# STM32F411CEU6.net
KiCad netlist of a schematic drawn in Altium Designer
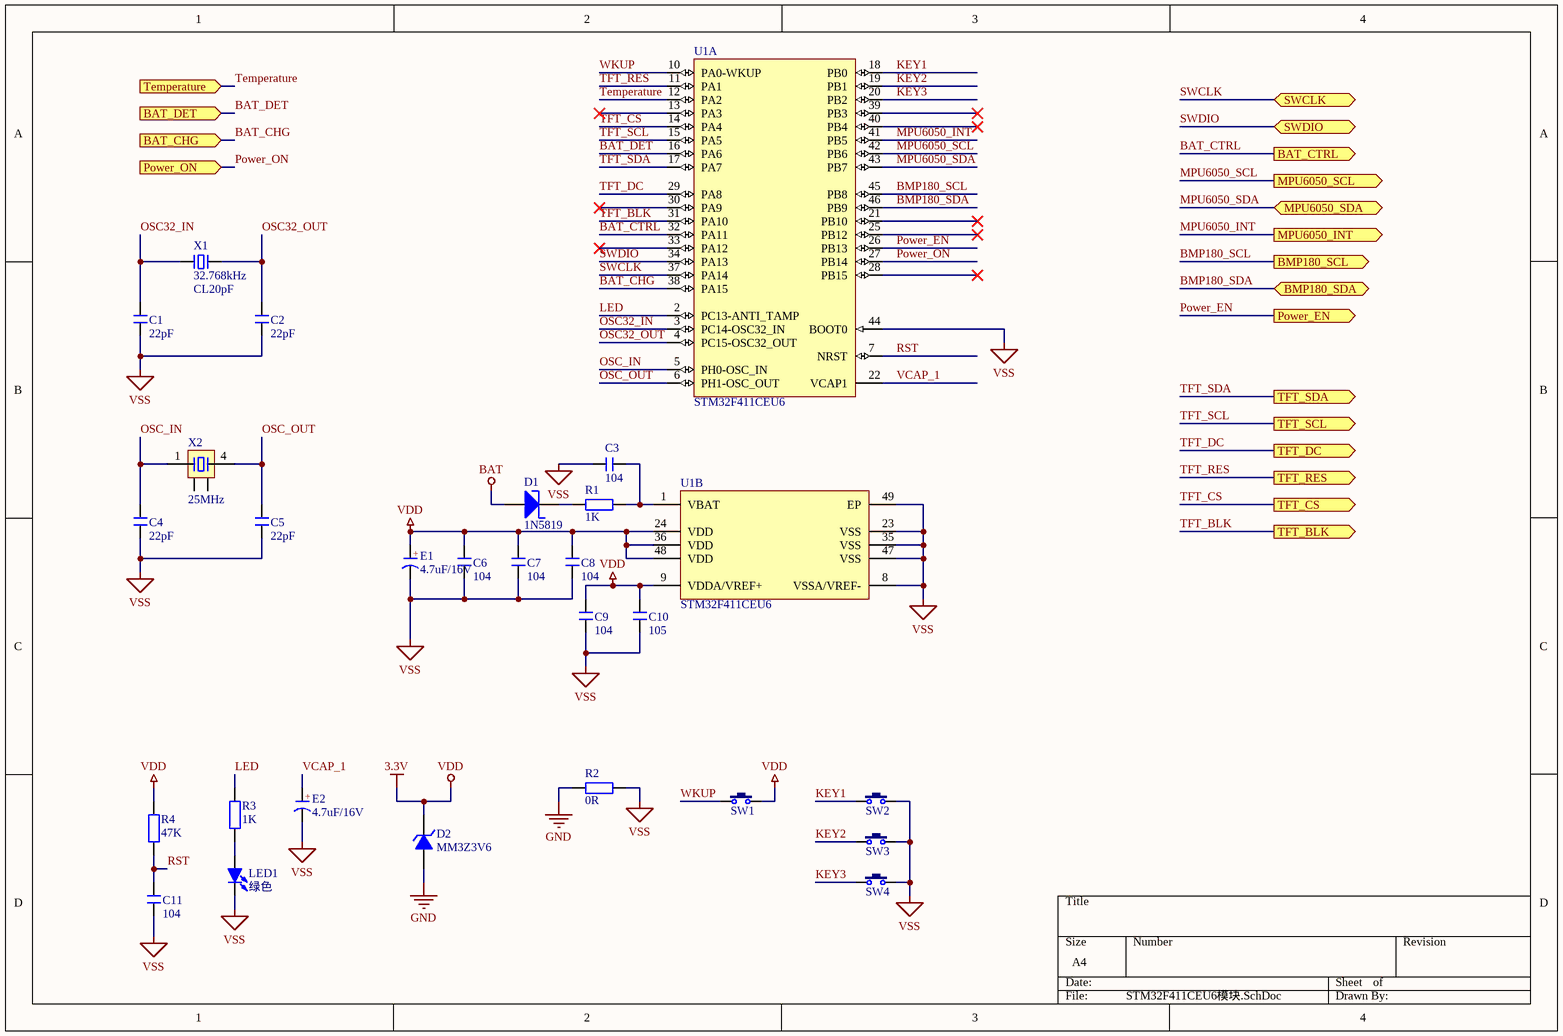
[diagram p0: STM32F411CEU6模块.SchDoc]

(export (version "E")
  (design (tool "Eeschema 10.0.6"))
  (components
    (comp (ref "C1")
      (value "22pF")
      (footprint "C 0402_M")
      (description "无极性贴片电容")
      (fields (field (name "版权归属") "黎明电子style"))
      (libsource (lib "3.3   - 电容capacitor") (part "C"))
    )
    (comp (ref "C2")
      (value "22pF")
      (footprint "C 0402_M")
      (description "无极性贴片电容")
      (fields (field (name "版权归属") "黎明电子style"))
      (libsource (lib "3.3   - 电容capacitor") (part "C"))
    )
    (comp (ref "C3")
      (value "104")
      (footprint "C 0603_L")
      (description "无极性贴片电容")
      (fields (field (name "版权归属") "黎明电子style"))
      (libsource (lib "3.3   - 电容capacitor") (part "C"))
    )
    (comp (ref "C4")
      (value "22pF")
      (footprint "C 0402_M")
      (description "无极性贴片电容")
      (fields (field (name "版权归属") "黎明电子style"))
      (libsource (lib "3.3   - 电容capacitor") (part "C"))
    )
    (comp (ref "C5")
      (value "22pF")
      (footprint "C 0402_M")
      (description "无极性贴片电容")
      (fields (field (name "版权归属") "黎明电子style"))
      (libsource (lib "3.3   - 电容capacitor") (part "C"))
    )
    (comp (ref "C6")
      (value "104")
      (footprint "C 0603_L")
      (description "无极性贴片电容")
      (fields (field (name "版权归属") "黎明电子style"))
      (libsource (lib "3.3   - 电容capacitor") (part "C"))
    )
    (comp (ref "C7")
      (value "104")
      (footprint "C 0603_L")
      (description "无极性贴片电容")
      (fields (field (name "版权归属") "黎明电子style"))
      (libsource (lib "3.3   - 电容capacitor") (part "C"))
    )
    (comp (ref "C8")
      (value "104")
      (footprint "C 0603_L")
      (description "无极性贴片电容")
      (fields (field (name "版权归属") "黎明电子style"))
      (libsource (lib "3.3   - 电容capacitor") (part "C"))
    )
    (comp (ref "C9")
      (value "104")
      (footprint "C 0603_L")
      (description "无极性贴片电容")
      (fields (field (name "版权归属") "黎明电子style"))
      (libsource (lib "3.3   - 电容capacitor") (part "C"))
    )
    (comp (ref "C10")
      (value "105")
      (footprint "C 0402_M")
      (description "无极性贴片电容")
      (fields (field (name "版权归属") "黎明电子style"))
      (libsource (lib "3.3   - 电容capacitor") (part "C"))
    )
    (comp (ref "C11")
      (value "104")
      (footprint "C 0603_L")
      (description "无极性贴片电容")
      (fields (field (name "版权归属") "黎明电子style"))
      (libsource (lib "3.3   - 电容capacitor") (part "C"))
    )
    (comp (ref "D1")
      (value "1N5819")
      (footprint "SOD-323")
      (description "肖特基二极管")
      (fields (field (name "版权归属") "源创客"))
      (libsource (lib "8.1   - 二极管-整流桥") (part "1N5819"))
    )
    (comp (ref "D2")
      (value "MM3Z3V6")
      (footprint "SOD-323")
      (description "3.6V/0.3W稳压管")
      (libsource (lib "8.1   - 二极管-整流桥") (part "MM3Z3V6"))
    )
    (comp (ref "E1")
      (value "4.7uF/16V")
      (footprint "CD A(3216)")
      (description "贴片钽电容")
      (fields (field (name "版权归属") "黎明电子style"))
      (libsource (lib "3.3   - 电容capacitor") (part "C-CD"))
    )
    (comp (ref "E2")
      (value "4.7uF/16V")
      (footprint "CD A(3216)")
      (description "贴片钽电容")
      (fields (field (name "版权归属") "黎明电子style"))
      (libsource (lib "3.3   - 电容capacitor") (part "C-CD"))
    )
    (comp (ref "LED1")
      (value "绿色")
      (footprint "LED 0603G")
      (description "贴片LED")
      (fields (field (name "版权归属") "源创客"))
      (libsource (lib "9.1   - LED") (part "LED-SMD"))
    )
    (comp (ref "R1")
      (value "1K")
      (footprint "R 0603_L")
      (description "贴片电阻")
      (fields (field (name "版权归属") "黎明电子style"))
      (libsource (lib "3.4   - 电阻Resistor") (part "R"))
    )
    (comp (ref "R2")
      (value "0R")
      (footprint "R 0603_L")
      (description "贴片电阻")
      (fields (field (name "版权归属") "黎明电子style"))
      (libsource (lib "3.4   - 电阻Resistor") (part "R"))
    )
    (comp (ref "R3")
      (value "1K")
      (footprint "R 0603_L")
      (description "贴片电阻")
      (fields (field (name "版权归属") "黎明电子style"))
      (libsource (lib "3.4   - 电阻Resistor") (part "R"))
    )
    (comp (ref "R4")
      (value "47K")
      (footprint "R 0603_L")
      (description "贴片电阻")
      (fields (field (name "版权归属") "黎明电子style"))
      (libsource (lib "3.4   - 电阻Resistor") (part "R"))
    )
    (comp (ref "SW1")
      (value "3x6x5")
      (footprint "TSW 4.6*1.82*3.5-S-W")
      (description "3x6轻触开关")
      (fields (field (name "版权归属") "源创客"))
      (libsource (lib "5.1   - 按键-开关") (part "TSW 3x6"))
    )
    (comp (ref "SW2")
      (value "3x6x5")
      (footprint "TSW 4.6*1.82*3.5-S-W")
      (description "3x6轻触开关")
      (fields (field (name "版权归属") "源创客"))
      (libsource (lib "5.1   - 按键-开关") (part "TSW 3x6"))
    )
    (comp (ref "SW3")
      (value "3x6x5")
      (footprint "TSW 4.6*1.82*3.5-S-W")
      (description "3x6轻触开关")
      (fields (field (name "版权归属") "源创客"))
      (libsource (lib "5.1   - 按键-开关") (part "TSW 3x6"))
    )
    (comp (ref "SW4")
      (value "3x6x5")
      (footprint "TSW 4.6*1.82*3.5-S-W")
      (description "3x6轻触开关")
      (fields (field (name "版权归属") "源创客"))
      (libsource (lib "5.1   - 按键-开关") (part "TSW 3x6"))
    )
    (comp (ref "U1")
      (value "STM32F411CEU6")
      (footprint "QFN48 7X7_N")
      (fields (field (name "MANUFACTURER") "STMicroelectronics") (field (name "PARTNUMBER") "STM32F401CCU6"))
      (libsource (lib "2.1   - STM32系列单片机") (part "STM32F411CEU6"))
    )
    (comp (ref "X1")
      (value "32.768kHz")
      (footprint "OSC 1016-2P")
      (description "2脚无源脚晶振")
      (fields (field (name "负载电容") "CL20pF") (field (name "版权归属") "源创客"))
      (libsource (lib "10.1 - 保险丝-晶振") (part "XTAL-2P"))
    )
    (comp (ref "X2")
      (value "25MHz")
      (footprint "OSC 1612-4P")
      (description "MC系列4脚晶振")
      (fields (field (name "版权归属") "源创客"))
      (libsource (lib "10.1 - 保险丝-晶振") (part "XTAL-MC-4P"))
    )
  )
  (nets
    (net (code "1") (name "/BAT_CHG") (class "Default")
      (node (ref "U1") (pin "38") (pinfunction "PA15_38") (pintype "bidirectional"))
    )
    (net (code "2") (name "/BAT_CTRL") (class "Default")
      (node (ref "U1") (pin "32") (pinfunction "PA11_32") (pintype "bidirectional"))
    )
    (net (code "3") (name "/BAT_DET") (class "Default")
      (node (ref "U1") (pin "16") (pinfunction "PA6_16") (pintype "bidirectional"))
    )
    (net (code "4") (name "/BMP180_SCL") (class "Default")
      (node (ref "U1") (pin "45") (pinfunction "PB8_45") (pintype "bidirectional"))
    )
    (net (code "5") (name "/BMP180_SDA") (class "Default")
      (node (ref "U1") (pin "46") (pinfunction "PB9_46") (pintype "bidirectional"))
    )
    (net (code "6") (name "/KEY1") (class "Default")
      (node (ref "SW2") (pin "1") (pinfunction "1_1") (pintype "passive"))
      (node (ref "U1") (pin "18") (pinfunction "PB0_18") (pintype "bidirectional"))
    )
    (net (code "7") (name "/KEY2") (class "Default")
      (node (ref "SW3") (pin "1") (pinfunction "1_1") (pintype "passive"))
      (node (ref "U1") (pin "19") (pinfunction "PB1_19") (pintype "bidirectional"))
    )
    (net (code "8") (name "/KEY3") (class "Default")
      (node (ref "SW4") (pin "1") (pinfunction "1_1") (pintype "passive"))
      (node (ref "U1") (pin "20") (pinfunction "PB2_20") (pintype "bidirectional"))
    )
    (net (code "9") (name "/LED") (class "Default")
      (node (ref "R3") (pin "2") (pinfunction "2_2") (pintype "passive"))
      (node (ref "U1") (pin "2") (pinfunction "PC13-ANTI_TAMP_2") (pintype "bidirectional"))
    )
    (net (code "10") (name "/MPU6050_INT") (class "Default")
      (node (ref "U1") (pin "41") (pinfunction "PB5_41") (pintype "bidirectional"))
    )
    (net (code "11") (name "/MPU6050_SCL") (class "Default")
      (node (ref "U1") (pin "42") (pinfunction "PB6_42") (pintype "bidirectional"))
    )
    (net (code "12") (name "/MPU6050_SDA") (class "Default")
      (node (ref "U1") (pin "43") (pinfunction "PB7_43") (pintype "bidirectional"))
    )
    (net (code "13") (name "/OSC32_IN") (class "Default")
      (node (ref "C1") (pin "2") (pinfunction "2_2") (pintype "passive"))
      (node (ref "U1") (pin "3") (pinfunction "PC14-OSC32_IN_3") (pintype "bidirectional"))
      (node (ref "X1") (pin "1") (pinfunction "1_1") (pintype "passive"))
    )
    (net (code "14") (name "/OSC32_OUT") (class "Default")
      (node (ref "C2") (pin "2") (pinfunction "2_2") (pintype "passive"))
      (node (ref "U1") (pin "4") (pinfunction "PC15-OSC32_OUT_4") (pintype "bidirectional"))
      (node (ref "X1") (pin "2") (pinfunction "2_2") (pintype "passive"))
    )
    (net (code "15") (name "/OSC_IN") (class "Default")
      (node (ref "C4") (pin "2") (pinfunction "2_2") (pintype "passive"))
      (node (ref "U1") (pin "5") (pinfunction "PH0-OSC_IN_5") (pintype "bidirectional"))
      (node (ref "X2") (pin "1") (pinfunction "1_1") (pintype "passive"))
    )
    (net (code "16") (name "/OSC_OUT") (class "Default")
      (node (ref "C5") (pin "2") (pinfunction "2_2") (pintype "passive"))
      (node (ref "U1") (pin "6") (pinfunction "PH1-OSC_OUT_6") (pintype "bidirectional"))
      (node (ref "X2") (pin "4") (pinfunction "4_4") (pintype "passive"))
    )
    (net (code "17") (name "/Power_EN") (class "Default")
      (node (ref "U1") (pin "26") (pinfunction "PB13_26") (pintype "bidirectional"))
    )
    (net (code "18") (name "/Power_ON") (class "Default")
      (node (ref "U1") (pin "27") (pinfunction "PB14_27") (pintype "bidirectional"))
    )
    (net (code "19") (name "/RST") (class "Default")
      (node (ref "C11") (pin "2") (pinfunction "2_2") (pintype "passive"))
      (node (ref "R4") (pin "1") (pinfunction "1_1") (pintype "passive"))
      (node (ref "U1") (pin "7") (pinfunction "NRST_7") (pintype "bidirectional"))
    )
    (net (code "20") (name "/SWCLK") (class "Default")
      (node (ref "U1") (pin "37") (pinfunction "PA14_37") (pintype "bidirectional"))
    )
    (net (code "21") (name "/SWDIO") (class "Default")
      (node (ref "U1") (pin "34") (pinfunction "PA13_34") (pintype "bidirectional"))
    )
    (net (code "22") (name "/TFT_BLK") (class "Default")
      (node (ref "U1") (pin "31") (pinfunction "PA10_31") (pintype "bidirectional"))
    )
    (net (code "23") (name "/TFT_CS") (class "Default")
      (node (ref "U1") (pin "14") (pinfunction "PA4_14") (pintype "bidirectional"))
    )
    (net (code "24") (name "/TFT_DC") (class "Default")
      (node (ref "U1") (pin "29") (pinfunction "PA8_29") (pintype "bidirectional"))
    )
    (net (code "25") (name "/TFT_RES") (class "Default")
      (node (ref "U1") (pin "11") (pinfunction "PA1_11") (pintype "bidirectional"))
    )
    (net (code "26") (name "/TFT_SCL") (class "Default")
      (node (ref "U1") (pin "15") (pinfunction "PA5_15") (pintype "bidirectional"))
    )
    (net (code "27") (name "/TFT_SDA") (class "Default")
      (node (ref "U1") (pin "17") (pinfunction "PA7_17") (pintype "bidirectional"))
    )
    (net (code "28") (name "/Temperature") (class "Default")
      (node (ref "U1") (pin "12") (pinfunction "PA2_12") (pintype "bidirectional"))
    )
    (net (code "29") (name "/VCAP_1") (class "Default")
      (node (ref "E2") (pin "1") (pinfunction "A_1") (pintype "passive"))
      (node (ref "U1") (pin "22") (pinfunction "VCAP1_22") (pintype "power_in"))
    )
    (net (code "30") (name "/WKUP") (class "Default")
      (node (ref "SW1") (pin "1") (pinfunction "1_1") (pintype "passive"))
      (node (ref "U1") (pin "10") (pinfunction "PA0-WKUP_10") (pintype "bidirectional"))
    )
    (net (code "31") (name "3.3V") (class "Default")
      (node (ref "C10") (pin "2") (pinfunction "2_2") (pintype "passive"))
      (node (ref "C6") (pin "2") (pinfunction "2_2") (pintype "passive"))
      (node (ref "C7") (pin "2") (pinfunction "2_2") (pintype "passive"))
      (node (ref "C8") (pin "2") (pinfunction "2_2") (pintype "passive"))
      (node (ref "C9") (pin "2") (pinfunction "2_2") (pintype "passive"))
      (node (ref "D2") (pin "2") (pinfunction "K_2") (pintype "passive"))
      (node (ref "E1") (pin "1") (pinfunction "A_1") (pintype "passive"))
      (node (ref "R4") (pin "2") (pinfunction "2_2") (pintype "passive"))
      (node (ref "SW1") (pin "2") (pinfunction "2_2") (pintype "passive"))
      (node (ref "U1") (pin "24") (pinfunction "VDD_24") (pintype "power_in"))
      (node (ref "U1") (pin "36") (pinfunction "VDD_36") (pintype "power_in"))
      (node (ref "U1") (pin "48") (pinfunction "VDD_48") (pintype "power_in"))
      (node (ref "U1") (pin "9") (pinfunction "VDDA/VREF+_9") (pintype "power_in"))
    )
    (net (code "32") (name "BAT") (class "Default")
      (node (ref "D1") (pin "1") (pinfunction "A_1") (pintype "passive"))
    )
    (net (code "33") (name "GND") (class "Default")
      (node (ref "D2") (pin "1") (pinfunction "A_1") (pintype "passive"))
      (node (ref "R2") (pin "2") (pinfunction "2_2") (pintype "passive"))
    )
    (net (code "34") (name "Net-(D1-K)") (class "Default")
      (node (ref "D1") (pin "2") (pinfunction "K_2") (pintype "passive"))
      (node (ref "R1") (pin "1") (pinfunction "1_1") (pintype "passive"))
    )
    (net (code "35") (name "Net-(LED1-A)") (class "Default")
      (node (ref "LED1") (pin "1") (pinfunction "A_1") (pintype "passive"))
      (node (ref "R3") (pin "1") (pinfunction "1_1") (pintype "passive"))
    )
    (net (code "36") (name "Net-(U1B-VBAT)") (class "Default")
      (node (ref "C3") (pin "1") (pinfunction "1_1") (pintype "passive"))
      (node (ref "R1") (pin "2") (pinfunction "2_2") (pintype "passive"))
      (node (ref "U1") (pin "1") (pinfunction "VBAT_1") (pintype "power_in"))
    )
    (net (code "37") (name "VSS") (class "Default")
      (node (ref "C1") (pin "1") (pinfunction "1_1") (pintype "passive"))
      (node (ref "C10") (pin "1") (pinfunction "1_1") (pintype "passive"))
      (node (ref "C11") (pin "1") (pinfunction "1_1") (pintype "passive"))
      (node (ref "C2") (pin "1") (pinfunction "1_1") (pintype "passive"))
      (node (ref "C3") (pin "2") (pinfunction "2_2") (pintype "passive"))
      (node (ref "C4") (pin "1") (pinfunction "1_1") (pintype "passive"))
      (node (ref "C5") (pin "1") (pinfunction "1_1") (pintype "passive"))
      (node (ref "C6") (pin "1") (pinfunction "1_1") (pintype "passive"))
      (node (ref "C7") (pin "1") (pinfunction "1_1") (pintype "passive"))
      (node (ref "C8") (pin "1") (pinfunction "1_1") (pintype "passive"))
      (node (ref "C9") (pin "1") (pinfunction "1_1") (pintype "passive"))
      (node (ref "E1") (pin "2") (pinfunction "K_2") (pintype "passive"))
      (node (ref "E2") (pin "2") (pinfunction "K_2") (pintype "passive"))
      (node (ref "LED1") (pin "2") (pinfunction "K_2") (pintype "passive"))
      (node (ref "R2") (pin "1") (pinfunction "1_1") (pintype "passive"))
      (node (ref "SW2") (pin "2") (pinfunction "2_2") (pintype "passive"))
      (node (ref "SW3") (pin "2") (pinfunction "2_2") (pintype "passive"))
      (node (ref "SW4") (pin "2") (pinfunction "2_2") (pintype "passive"))
      (node (ref "U1") (pin "23") (pinfunction "VSS_23") (pintype "power_in"))
      (node (ref "U1") (pin "35") (pinfunction "VSS_35") (pintype "power_in"))
      (node (ref "U1") (pin "44") (pinfunction "BOOT0_44") (pintype "input"))
      (node (ref "U1") (pin "47") (pinfunction "VSS_47") (pintype "power_in"))
      (node (ref "U1") (pin "49") (pinfunction "EP_49") (pintype "power_in"))
      (node (ref "U1") (pin "8") (pinfunction "VSSA/VREF-_8") (pintype "power_in"))
    )
    (net (code "38") (name "unconnected-(U1A-PA3-Pad13)") (class "Default")
      (node (ref "U1") (pin "13") (pinfunction "PA3_13") (pintype "bidirectional+no_connect"))
    )
    (net (code "39") (name "unconnected-(U1A-PA9-Pad30)") (class "Default")
      (node (ref "U1") (pin "30") (pinfunction "PA9_30") (pintype "bidirectional+no_connect"))
    )
    (net (code "40") (name "unconnected-(U1A-PA12-Pad33)") (class "Default")
      (node (ref "U1") (pin "33") (pinfunction "PA12_33") (pintype "bidirectional+no_connect"))
    )
    (net (code "41") (name "unconnected-(U1A-PB3-Pad39)") (class "Default")
      (node (ref "U1") (pin "39") (pinfunction "PB3_39") (pintype "bidirectional+no_connect"))
    )
    (net (code "42") (name "unconnected-(U1A-PB4-Pad40)") (class "Default")
      (node (ref "U1") (pin "40") (pinfunction "PB4_40") (pintype "bidirectional+no_connect"))
    )
    (net (code "43") (name "unconnected-(U1A-PB10-Pad21)") (class "Default")
      (node (ref "U1") (pin "21") (pinfunction "PB10_21") (pintype "bidirectional+no_connect"))
    )
    (net (code "44") (name "unconnected-(U1A-PB12-Pad25)") (class "Default")
      (node (ref "U1") (pin "25") (pinfunction "PB12_25") (pintype "bidirectional+no_connect"))
    )
    (net (code "45") (name "unconnected-(U1A-PB15-Pad28)") (class "Default")
      (node (ref "U1") (pin "28") (pinfunction "PB15_28") (pintype "bidirectional+no_connect"))
    )
    (net (code "46") (name "unconnected-(X2-Pad2)") (class "Default")
      (node (ref "X2") (pin "2") (pinfunction "2_2") (pintype "passive"))
    )
    (net (code "47") (name "unconnected-(X2-Pad3)") (class "Default")
      (node (ref "X2") (pin "3") (pinfunction "3_3") (pintype "passive"))
    )
  )
)
